# sensor9dof.net
KiCad netlist of a schematic drawn in EAGLE
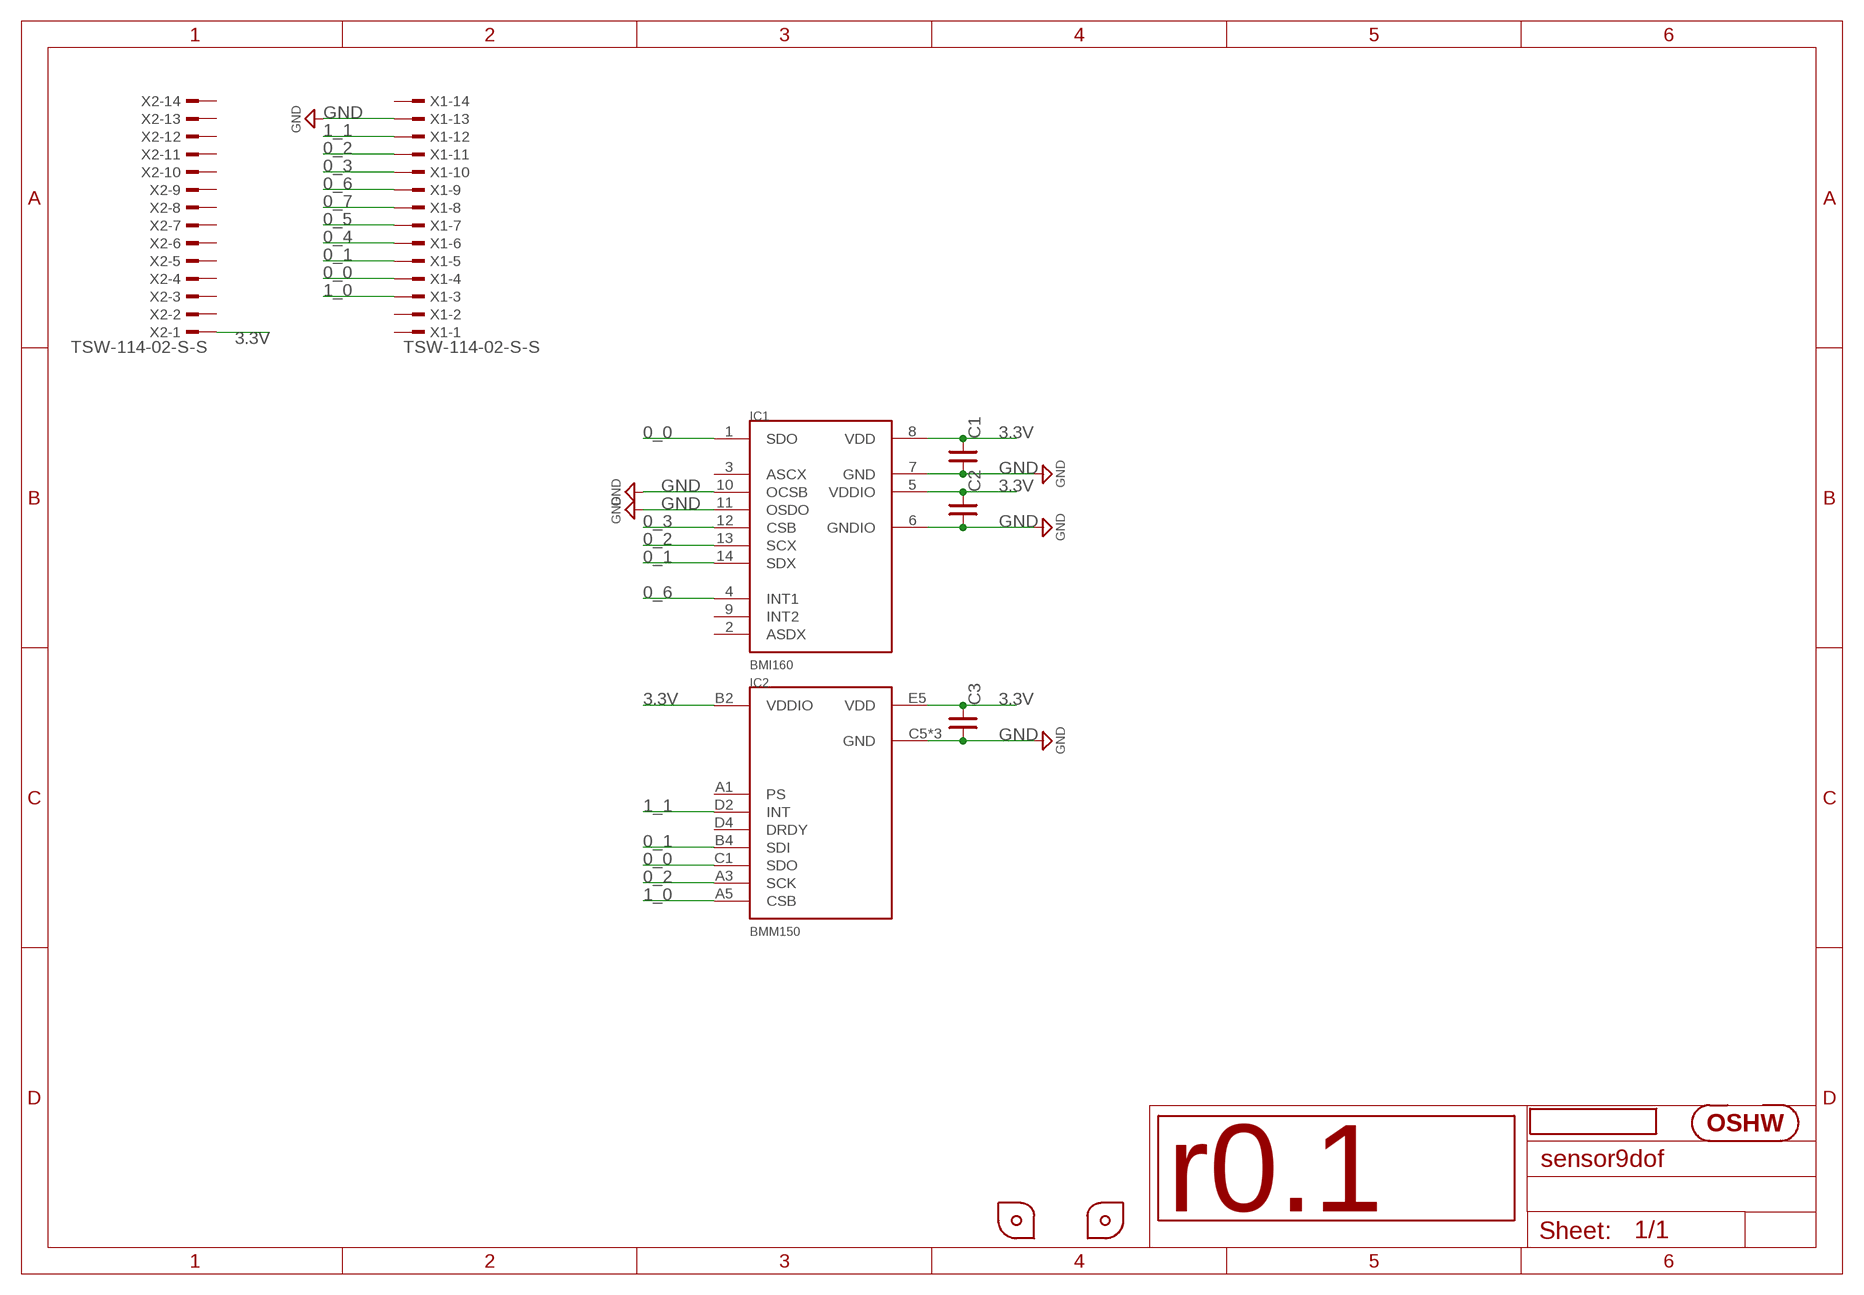
[diagram p0: schematic, sheet 1]

(export (version "E")
  (design (tool "Eeschema 10.0.6"))
  (components
    (comp (ref "C1")
      (value "C_SMD_0.1U_1005")
      (footprint "eagle-import:C0402")
      (libsource (lib "eagle-import") (part "C_SMD__10050.1U"))
    )
    (comp (ref "C2")
      (value "C_SMD_0.1U_1005")
      (footprint "eagle-import:C0402")
      (libsource (lib "eagle-import") (part "C_SMD__10050.1U"))
    )
    (comp (ref "C3")
      (value "C_SMD_0.1U_1005")
      (footprint "eagle-import:C0402")
      (libsource (lib "eagle-import") (part "C_SMD__10050.1U"))
    )
    (comp (ref "GIT1")
      (value "GIT-REVISION_1.0")
      (footprint "eagle-import:GIT-REVISION")
      (libsource (lib "eagle-import") (part "GIT-REVISION_1.0"))
    )
    (comp (ref "IC1")
      (value "BMI160")
      (footprint "eagle-import:BMI160")
      (libsource (lib "eagle-import") (part "BMI160"))
    )
    (comp (ref "IC2")
      (value "BMM150")
      (footprint "eagle-import:BMM150")
      (libsource (lib "eagle-import") (part "BMM150"))
    )
    (comp (ref "ICON1")
      (value "ICON_OSHW")
      (footprint "eagle-import:ICON_OSHW")
      (libsource (lib "eagle-import") (part "ICON_OSHW"))
    )
    (comp (ref "ICON2")
      (value "r0.1")
      (footprint "eagle-import:ICON_REVISION2.0")
      (libsource (lib "eagle-import") (part "ICON_REVISION_2.0"))
    )
    (comp (ref "P5")
      (value "PCB_CORNER_NH")
      (footprint "eagle-import:PCB_CORNER_NH")
      (libsource (lib "eagle-import") (part "PCB_CORNER_NH"))
    )
    (comp (ref "P6")
      (value "PCB_CORNER")
      (footprint "eagle-import:PCB_CORNER")
      (libsource (lib "eagle-import") (part "PCB_CORNER"))
    )
    (comp (ref "X1")
      (value "TSW-114-02-S-S")
      (footprint "eagle-import:TSW-114-07-F-S")
      (libsource (lib "eagle-import") (part "TSW-114-02-S-S"))
    )
    (comp (ref "X2")
      (value "TSW-114-02-S-S")
      (footprint "eagle-import:TSW-114-07-F-S")
      (libsource (lib "eagle-import") (part "TSW-114-02-S-S"))
    )
  )
  (nets
    (net (code "1") (name "/0_0") (class "Default")
      (node (ref "IC1") (pin "1") (pinfunction "SDO_1") (pintype "bidirectional"))
      (node (ref "IC2") (pin "C1") (pinfunction "SDO_C1") (pintype "bidirectional"))
      (node (ref "X1") (pin "4") (pinfunction "1_4") (pintype "passive"))
    )
    (net (code "2") (name "/0_1") (class "Default")
      (node (ref "IC1") (pin "14") (pinfunction "SDX_14") (pintype "bidirectional"))
      (node (ref "IC2") (pin "B4") (pinfunction "SDI_B4") (pintype "bidirectional"))
      (node (ref "X1") (pin "5") (pinfunction "1_5") (pintype "passive"))
    )
    (net (code "3") (name "/0_2") (class "Default")
      (node (ref "IC1") (pin "13") (pinfunction "SCX_13") (pintype "bidirectional"))
      (node (ref "IC2") (pin "A3") (pinfunction "SCK_A3") (pintype "bidirectional"))
      (node (ref "X1") (pin "11") (pinfunction "1_11") (pintype "passive"))
    )
    (net (code "4") (name "/0_3") (class "Default")
      (node (ref "IC1") (pin "12") (pinfunction "CSB_12") (pintype "bidirectional"))
      (node (ref "X1") (pin "10") (pinfunction "1_10") (pintype "passive"))
    )
    (net (code "5") (name "/0_4") (class "Default")
      (node (ref "X1") (pin "6") (pinfunction "1_6") (pintype "passive"))
    )
    (net (code "6") (name "/0_5") (class "Default")
      (node (ref "X1") (pin "7") (pinfunction "1_7") (pintype "passive"))
    )
    (net (code "7") (name "/0_6") (class "Default")
      (node (ref "IC1") (pin "4") (pinfunction "INT1_4") (pintype "bidirectional"))
      (node (ref "X1") (pin "9") (pinfunction "1_9") (pintype "passive"))
    )
    (net (code "8") (name "/0_7") (class "Default")
      (node (ref "X1") (pin "8") (pinfunction "1_8") (pintype "passive"))
    )
    (net (code "9") (name "/1_0") (class "Default")
      (node (ref "IC2") (pin "A5") (pinfunction "CSB_A5") (pintype "bidirectional"))
      (node (ref "X1") (pin "3") (pinfunction "1_3") (pintype "passive"))
    )
    (net (code "10") (name "/1_1") (class "Default")
      (node (ref "IC2") (pin "D2") (pinfunction "INT_D2") (pintype "bidirectional"))
      (node (ref "X1") (pin "12") (pinfunction "1_12") (pintype "passive"))
    )
    (net (code "11") (name "/3.3V") (class "Default")
      (node (ref "C1") (pin "1") (pinfunction "1_1") (pintype "passive"))
      (node (ref "C2") (pin "1") (pinfunction "1_1") (pintype "passive"))
      (node (ref "C3") (pin "1") (pinfunction "1_1") (pintype "passive"))
      (node (ref "IC1") (pin "5") (pinfunction "VDDIO_5") (pintype "power_in"))
      (node (ref "IC1") (pin "8") (pinfunction "VDD_8") (pintype "power_in"))
      (node (ref "IC2") (pin "B2") (pinfunction "VDDIO_B2") (pintype "power_in"))
      (node (ref "IC2") (pin "E5") (pinfunction "VDD_E5") (pintype "power_in"))
      (node (ref "X2") (pin "1") (pinfunction "1_1") (pintype "passive"))
    )
    (net (code "12") (name "GND") (class "Default")
      (node (ref "C1") (pin "2") (pinfunction "2_2") (pintype "passive"))
      (node (ref "C2") (pin "2") (pinfunction "2_2") (pintype "passive"))
      (node (ref "C3") (pin "2") (pinfunction "2_2") (pintype "passive"))
      (node (ref "IC1") (pin "10") (pinfunction "OCSB_10") (pintype "bidirectional"))
      (node (ref "IC1") (pin "11") (pinfunction "OSDO_11") (pintype "bidirectional"))
      (node (ref "IC1") (pin "6") (pinfunction "GNDIO_6") (pintype "passive"))
      (node (ref "IC1") (pin "7") (pinfunction "GND_7") (pintype "passive"))
      (node (ref "IC2") (pin "C5") (pinfunction "GND_C5") (pintype "passive"))
      (node (ref "IC2") (pin "E1") (pinfunction "GND_E1") (pintype "passive"))
      (node (ref "IC2") (pin "E3") (pinfunction "GND_E3") (pintype "passive"))
      (node (ref "X1") (pin "13") (pinfunction "1_13") (pintype "passive"))
    )
    (net (code "13") (name "unconnected-(IC1-ASCX-Pad3)") (class "Default")
      (node (ref "IC1") (pin "3") (pinfunction "ASCX_3") (pintype "bidirectional"))
    )
    (net (code "14") (name "unconnected-(IC1-ASDX-Pad2)") (class "Default")
      (node (ref "IC1") (pin "2") (pinfunction "ASDX_2") (pintype "bidirectional"))
    )
    (net (code "15") (name "unconnected-(IC1-INT2-Pad9)") (class "Default")
      (node (ref "IC1") (pin "9") (pinfunction "INT2_9") (pintype "bidirectional"))
    )
    (net (code "16") (name "unconnected-(IC2-DRDY-PadD4)") (class "Default")
      (node (ref "IC2") (pin "D4") (pinfunction "DRDY_D4") (pintype "bidirectional"))
    )
    (net (code "17") (name "unconnected-(IC2-PS-PadA1)") (class "Default")
      (node (ref "IC2") (pin "A1") (pinfunction "PS_A1") (pintype "bidirectional"))
    )
    (net (code "18") (name "unconnected-(X1-Pad1)") (class "Default")
      (node (ref "X1") (pin "1") (pinfunction "1_1") (pintype "passive"))
    )
    (net (code "19") (name "unconnected-(X1F-1-Pad14)") (class "Default")
      (node (ref "X1") (pin "14") (pinfunction "1_14") (pintype "passive"))
    )
    (net (code "20") (name "unconnected-(X1G-1-Pad2)") (class "Default")
      (node (ref "X1") (pin "2") (pinfunction "1_2") (pintype "passive"))
    )
    (net (code "21") (name "unconnected-(X2B-1-Pad10)") (class "Default")
      (node (ref "X2") (pin "10") (pinfunction "1_10") (pintype "passive"))
    )
    (net (code "22") (name "unconnected-(X2C-1-Pad11)") (class "Default")
      (node (ref "X2") (pin "11") (pinfunction "1_11") (pintype "passive"))
    )
    (net (code "23") (name "unconnected-(X2D-1-Pad12)") (class "Default")
      (node (ref "X2") (pin "12") (pinfunction "1_12") (pintype "passive"))
    )
    (net (code "24") (name "unconnected-(X2E-1-Pad13)") (class "Default")
      (node (ref "X2") (pin "13") (pinfunction "1_13") (pintype "passive"))
    )
    (net (code "25") (name "unconnected-(X2F-1-Pad14)") (class "Default")
      (node (ref "X2") (pin "14") (pinfunction "1_14") (pintype "passive"))
    )
    (net (code "26") (name "unconnected-(X2G-1-Pad2)") (class "Default")
      (node (ref "X2") (pin "2") (pinfunction "1_2") (pintype "passive"))
    )
    (net (code "27") (name "unconnected-(X2H-1-Pad3)") (class "Default")
      (node (ref "X2") (pin "3") (pinfunction "1_3") (pintype "passive"))
    )
    (net (code "28") (name "unconnected-(X2I-1-Pad4)") (class "Default")
      (node (ref "X2") (pin "4") (pinfunction "1_4") (pintype "passive"))
    )
    (net (code "29") (name "unconnected-(X2J-1-Pad5)") (class "Default")
      (node (ref "X2") (pin "5") (pinfunction "1_5") (pintype "passive"))
    )
    (net (code "30") (name "unconnected-(X2K-1-Pad6)") (class "Default")
      (node (ref "X2") (pin "6") (pinfunction "1_6") (pintype "passive"))
    )
    (net (code "31") (name "unconnected-(X2L-1-Pad7)") (class "Default")
      (node (ref "X2") (pin "7") (pinfunction "1_7") (pintype "passive"))
    )
    (net (code "32") (name "unconnected-(X2M-1-Pad8)") (class "Default")
      (node (ref "X2") (pin "8") (pinfunction "1_8") (pintype "passive"))
    )
    (net (code "33") (name "unconnected-(X2N-1-Pad9)") (class "Default")
      (node (ref "X2") (pin "9") (pinfunction "1_9") (pintype "passive"))
    )
  )
)
